# weichen-a-2.net
KiCad netlist of a schematic drawn in EAGLE
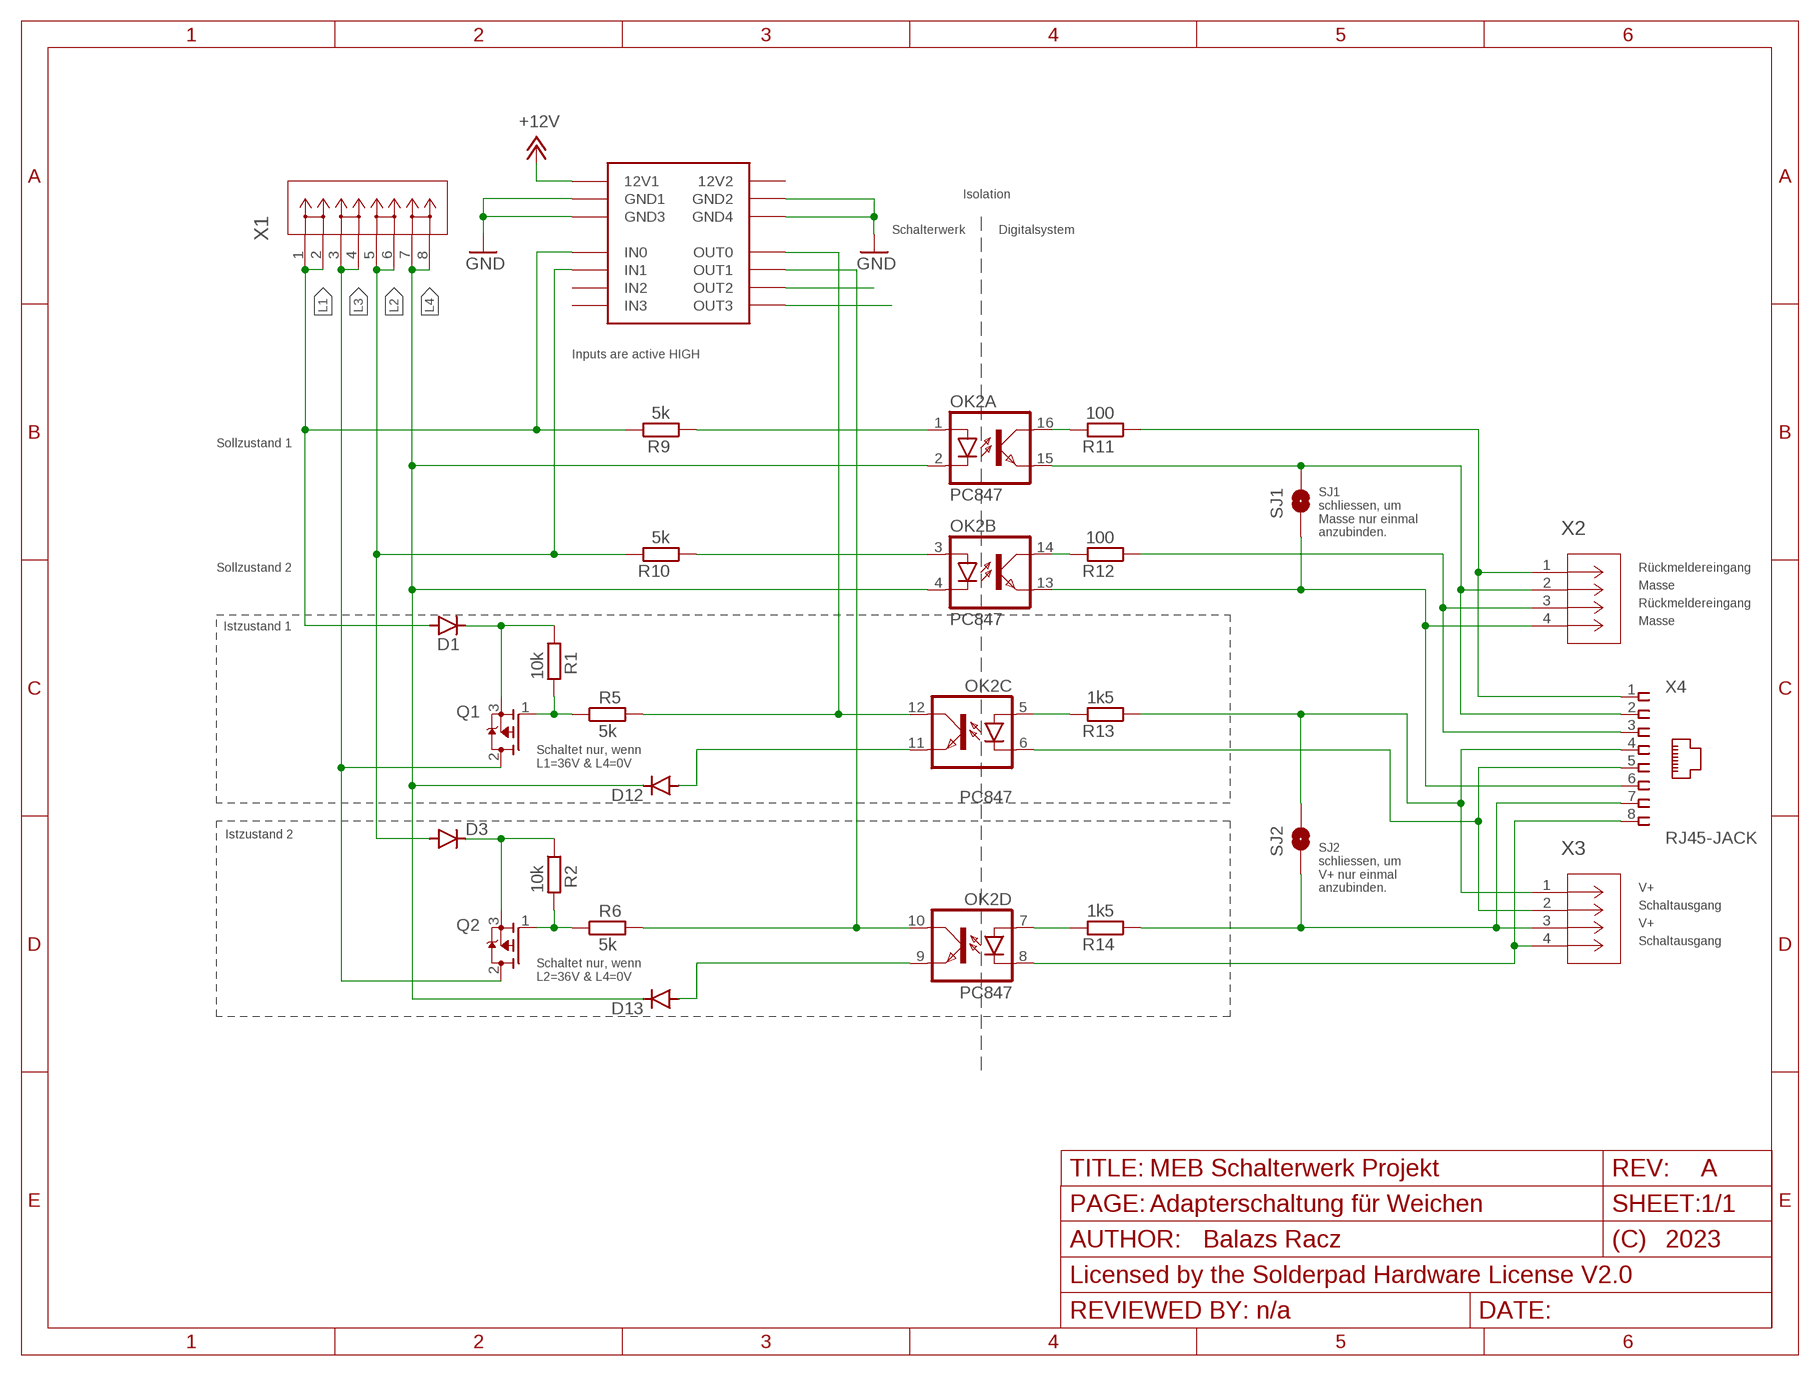
[diagram p0: schematic, sheet 1]

(export (version "E")
  (design (tool "Eeschema 10.0.6"))
  (components
    (comp (ref "D1")
      (value "DIODE-DO214AC")
      (footprint "eagle-import:DO214AC")
      (libsource (lib "eagle-import") (part "DIODE-DO214AC"))
    )
    (comp (ref "D3")
      (value "DIODE-DO214AC")
      (footprint "eagle-import:DO214AC")
      (libsource (lib "eagle-import") (part "DIODE-DO214AC"))
    )
    (comp (ref "D12")
      (value "DIODE-MINIMELF")
      (footprint "eagle-import:MINIMELF")
      (libsource (lib "eagle-import") (part "DIODE-MINIMELF"))
    )
    (comp (ref "D13")
      (value "DIODE-MINIMELF")
      (footprint "eagle-import:MINIMELF")
      (libsource (lib "eagle-import") (part "DIODE-MINIMELF"))
    )
    (comp (ref "OK2")
      (value "PC847")
      (footprint "eagle-import:DIL16")
      (libsource (lib "eagle-import") (part "PC847"))
    )
    (comp (ref "Q1")
      (value "P-MOSFET")
      (footprint "eagle-import:DPAK-2")
      (fields (field (name "MANUFACTURER") "Infineon"))
      (libsource (lib "eagle-import") (part "P-MOSFET"))
    )
    (comp (ref "Q2")
      (value "P-MOSFET")
      (footprint "eagle-import:DPAK-2")
      (fields (field (name "MANUFACTURER") "Infineon"))
      (libsource (lib "eagle-import") (part "P-MOSFET"))
    )
    (comp (ref "R1")
      (value "10k")
      (footprint "eagle-import:R0805")
      (libsource (lib "eagle-import") (part "R-EU_R0805"))
    )
    (comp (ref "R2")
      (value "10k")
      (footprint "eagle-import:R0805")
      (libsource (lib "eagle-import") (part "R-EU_R0805"))
    )
    (comp (ref "R5")
      (value "5k")
      (footprint "eagle-import:R0805")
      (libsource (lib "eagle-import") (part "R-EU_R0805"))
    )
    (comp (ref "R6")
      (value "5k")
      (footprint "eagle-import:R0805")
      (libsource (lib "eagle-import") (part "R-EU_R0805"))
    )
    (comp (ref "R9")
      (value "5k")
      (footprint "eagle-import:R0805")
      (libsource (lib "eagle-import") (part "R-EU_R0805"))
    )
    (comp (ref "R10")
      (value "5k")
      (footprint "eagle-import:R0805")
      (libsource (lib "eagle-import") (part "R-EU_R0805"))
    )
    (comp (ref "R11")
      (value "100")
      (footprint "eagle-import:R0805")
      (libsource (lib "eagle-import") (part "R-EU_R0805"))
    )
    (comp (ref "R12")
      (value "100")
      (footprint "eagle-import:R0805")
      (libsource (lib "eagle-import") (part "R-EU_R0805"))
    )
    (comp (ref "R13")
      (value "1k5")
      (footprint "eagle-import:R0805")
      (libsource (lib "eagle-import") (part "R-EU_R0805"))
    )
    (comp (ref "R14")
      (value "1k5")
      (footprint "eagle-import:R0805")
      (libsource (lib "eagle-import") (part "R-EU_R0805"))
    )
    (comp (ref "SJ1")
      (value "SJRND2")
      (footprint "eagle-import:SJ_RND2")
      (libsource (lib "eagle-import") (part "SJRND2"))
    )
    (comp (ref "SJ2")
      (value "SJRND2")
      (footprint "eagle-import:SJ_RND2")
      (libsource (lib "eagle-import") (part "SJRND2"))
    )
    (comp (ref "X1")
      (value "PHNX_4P_508CONN_1017493")
      (footprint "eagle-import:PHNX_4P_508")
      (fields
        (field (name "MANUFACTURER_PART_NUMBER") "1017505")
        (field (name "COPYRIGHT") "Copyright (C) 2023 Ultra Librarian. All rights reserved.")
      )
      (libsource (lib "eagle-import") (part "PHNX_4P_508CONN_1017493"))
    )
    (comp (ref "X2")
      (value "PHNX_4P_350CONN_1984989_PXC")
      (footprint "eagle-import:PHNX_4P_350")
      (fields
        (field (name "MANUFACTURER_PART_NUMBER") "1984989")
        (field (name "COPYRIGHT") "Copyright (C) 2023 Ultra Librarian. All rights reserved.")
      )
      (libsource (lib "eagle-import") (part "PHNX_4P_350CONN_1984989_PXC"))
    )
    (comp (ref "X3")
      (value "PHNX_4P_350CONN_1984989_PXC")
      (footprint "eagle-import:PHNX_4P_350")
      (fields
        (field (name "MANUFACTURER_PART_NUMBER") "1984989")
        (field (name "COPYRIGHT") "Copyright (C) 2023 Ultra Librarian. All rights reserved.")
      )
      (libsource (lib "eagle-import") (part "PHNX_4P_350CONN_1984989_PXC"))
    )
    (comp (ref "X4")
      (value "RJ45-JACK")
      (footprint "eagle-import:RJ45-PULSE-E5J88")
      (libsource (lib "eagle-import") (part "RJ45-JACKRJ45-PULSE-E5J00"))
    )
    (comp (ref "X5")
      (value "IO-HAT")
      (footprint "eagle-import:IOBOARD")
      (libsource (lib "eagle-import") (part "IO-HAT"))
    )
  )
  (nets
    (net (code "1") (name "+12V") (class "Default")
      (node (ref "X5") (pin "P$1") (pinfunction "12V1_P$1") (pintype "power_in"))
    )
    (net (code "2") (name "/12V2") (class "Default")
      (node (ref "X5") (pin "P$22") (pinfunction "12V2_P$22") (pintype "power_in"))
    )
    (net (code "3") (name "GND") (class "Default")
      (node (ref "X5") (pin "P$11") (pinfunction "GND3_P$11") (pintype "power_in"))
      (node (ref "X5") (pin "P$12") (pinfunction "GND4_P$12") (pintype "power_in"))
      (node (ref "X5") (pin "P$2") (pinfunction "GND1_P$2") (pintype "power_in"))
      (node (ref "X5") (pin "P$21") (pinfunction "GND2_P$21") (pintype "power_in"))
    )
    (net (code "4") (name "L1") (class "Default")
      (node (ref "D1") (pin "A") (pinfunction "A_A") (pintype "passive"))
      (node (ref "R9") (pin "2") (pinfunction "2_2") (pintype "passive"))
      (node (ref "X1") (pin "1") (pinfunction "1_1") (pintype "passive"))
      (node (ref "X1") (pin "2") (pinfunction "2_2") (pintype "passive"))
      (node (ref "X5") (pin "P$3") (pinfunction "IN0_P$3") (pintype "input"))
    )
    (net (code "5") (name "L2") (class "Default")
      (node (ref "D3") (pin "A") (pinfunction "A_A") (pintype "passive"))
      (node (ref "R10") (pin "2") (pinfunction "2_2") (pintype "passive"))
      (node (ref "X1") (pin "5") (pinfunction "5_5") (pintype "passive"))
      (node (ref "X1") (pin "6") (pinfunction "6_6") (pintype "passive"))
      (node (ref "X5") (pin "P$4") (pinfunction "IN1_P$4") (pintype "input"))
    )
    (net (code "6") (name "L3") (class "Default")
      (node (ref "Q1") (pin "2") (pinfunction "D_2") (pintype "passive"))
      (node (ref "Q2") (pin "2") (pinfunction "D_2") (pintype "passive"))
      (node (ref "X1") (pin "3") (pinfunction "3_3") (pintype "passive"))
      (node (ref "X1") (pin "4") (pinfunction "4_4") (pintype "passive"))
    )
    (net (code "7") (name "L4") (class "Default")
      (node (ref "D12") (pin "C") (pinfunction "C_C") (pintype "passive"))
      (node (ref "D13") (pin "C") (pinfunction "C_C") (pintype "passive"))
      (node (ref "OK2") (pin "2") (pinfunction "C_2") (pintype "passive"))
      (node (ref "OK2") (pin "4") (pinfunction "C_4") (pintype "passive"))
      (node (ref "X1") (pin "7") (pinfunction "7_7") (pintype "passive"))
      (node (ref "X1") (pin "8") (pinfunction "8_8") (pintype "passive"))
    )
    (net (code "8") (name "Net-(OK2A-A)") (class "Default")
      (node (ref "OK2") (pin "1") (pinfunction "A_1") (pintype "passive"))
      (node (ref "R9") (pin "1") (pinfunction "1_1") (pintype "passive"))
    )
    (net (code "9") (name "Net-(OK2A-COL)") (class "Default")
      (node (ref "OK2") (pin "16") (pinfunction "COL_16") (pintype "passive"))
      (node (ref "R11") (pin "2") (pinfunction "2_2") (pintype "passive"))
    )
    (net (code "10") (name "Net-(OK2A-EMIT)") (class "Default")
      (node (ref "OK2") (pin "15") (pinfunction "EMIT_15") (pintype "passive"))
      (node (ref "SJ1") (pin "P$2") (pinfunction "2_P$2") (pintype "passive"))
      (node (ref "X2") (pin "2") (pinfunction "2_2") (pintype "passive"))
      (node (ref "X4") (pin "2") (pinfunction "2_2") (pintype "passive"))
    )
    (net (code "11") (name "Net-(OK2B-A)") (class "Default")
      (node (ref "OK2") (pin "3") (pinfunction "A_3") (pintype "passive"))
      (node (ref "R10") (pin "1") (pinfunction "1_1") (pintype "passive"))
    )
    (net (code "12") (name "Net-(OK2B-COL)") (class "Default")
      (node (ref "OK2") (pin "14") (pinfunction "COL_14") (pintype "passive"))
      (node (ref "R12") (pin "2") (pinfunction "2_2") (pintype "passive"))
    )
    (net (code "13") (name "Net-(OK2B-EMIT)") (class "Default")
      (node (ref "OK2") (pin "13") (pinfunction "EMIT_13") (pintype "passive"))
      (node (ref "SJ1") (pin "P$1") (pinfunction "1_P$1") (pintype "passive"))
      (node (ref "X2") (pin "4") (pinfunction "4_4") (pintype "passive"))
      (node (ref "X4") (pin "6") (pinfunction "6_6") (pintype "passive"))
    )
    (net (code "14") (name "Net-(OK2C-A)") (class "Default")
      (node (ref "OK2") (pin "5") (pinfunction "A_5") (pintype "passive"))
      (node (ref "R13") (pin "2") (pinfunction "2_2") (pintype "passive"))
    )
    (net (code "15") (name "Net-(OK2C-C)") (class "Default")
      (node (ref "OK2") (pin "6") (pinfunction "C_6") (pintype "passive"))
      (node (ref "X3") (pin "2") (pinfunction "2_2") (pintype "passive"))
      (node (ref "X4") (pin "5") (pinfunction "5_5") (pintype "passive"))
    )
    (net (code "16") (name "Net-(OK2C-COL)") (class "Default")
      (node (ref "OK2") (pin "12") (pinfunction "COL_12") (pintype "passive"))
      (node (ref "R5") (pin "2") (pinfunction "2_2") (pintype "passive"))
      (node (ref "X5") (pin "P$20") (pinfunction "OUT0_P$20") (pintype "open_collector"))
    )
    (net (code "17") (name "Net-(OK2C-EMIT)") (class "Default")
      (node (ref "D12") (pin "A") (pinfunction "A_A") (pintype "passive"))
      (node (ref "OK2") (pin "11") (pinfunction "EMIT_11") (pintype "passive"))
    )
    (net (code "18") (name "Net-(OK2D-A)") (class "Default")
      (node (ref "OK2") (pin "7") (pinfunction "A_7") (pintype "passive"))
      (node (ref "R14") (pin "2") (pinfunction "2_2") (pintype "passive"))
    )
    (net (code "19") (name "Net-(OK2D-C)") (class "Default")
      (node (ref "OK2") (pin "8") (pinfunction "C_8") (pintype "passive"))
      (node (ref "X3") (pin "4") (pinfunction "4_4") (pintype "passive"))
      (node (ref "X4") (pin "8") (pinfunction "8_8") (pintype "passive"))
    )
    (net (code "20") (name "Net-(OK2D-COL)") (class "Default")
      (node (ref "OK2") (pin "10") (pinfunction "COL_10") (pintype "passive"))
      (node (ref "R6") (pin "2") (pinfunction "2_2") (pintype "passive"))
      (node (ref "X5") (pin "P$19") (pinfunction "OUT1_P$19") (pintype "open_collector"))
    )
    (net (code "21") (name "Net-(OK2D-EMIT)") (class "Default")
      (node (ref "D13") (pin "A") (pinfunction "A_A") (pintype "passive"))
      (node (ref "OK2") (pin "9") (pinfunction "EMIT_9") (pintype "passive"))
    )
    (net (code "22") (name "Net-(Q1-G)") (class "Default")
      (node (ref "Q1") (pin "1") (pinfunction "G_1") (pintype "passive"))
      (node (ref "R1") (pin "2") (pinfunction "2_2") (pintype "passive"))
      (node (ref "R5") (pin "1") (pinfunction "1_1") (pintype "passive"))
    )
    (net (code "23") (name "Net-(Q1-S)") (class "Default")
      (node (ref "D1") (pin "C") (pinfunction "C_C") (pintype "passive"))
      (node (ref "Q1") (pin "3") (pinfunction "S_3") (pintype "passive"))
      (node (ref "R1") (pin "1") (pinfunction "1_1") (pintype "passive"))
    )
    (net (code "24") (name "Net-(Q2-G)") (class "Default")
      (node (ref "Q2") (pin "1") (pinfunction "G_1") (pintype "passive"))
      (node (ref "R2") (pin "2") (pinfunction "2_2") (pintype "passive"))
      (node (ref "R6") (pin "1") (pinfunction "1_1") (pintype "passive"))
    )
    (net (code "25") (name "Net-(Q2-S)") (class "Default")
      (node (ref "D3") (pin "C") (pinfunction "C_C") (pintype "passive"))
      (node (ref "Q2") (pin "3") (pinfunction "S_3") (pintype "passive"))
      (node (ref "R2") (pin "1") (pinfunction "1_1") (pintype "passive"))
    )
    (net (code "26") (name "Net-(R11-Pad1)") (class "Default")
      (node (ref "R11") (pin "1") (pinfunction "1_1") (pintype "passive"))
      (node (ref "X2") (pin "1") (pinfunction "1_1") (pintype "passive"))
      (node (ref "X4") (pin "1") (pinfunction "1_1") (pintype "passive"))
    )
    (net (code "27") (name "Net-(R12-Pad1)") (class "Default")
      (node (ref "R12") (pin "1") (pinfunction "1_1") (pintype "passive"))
      (node (ref "X2") (pin "3") (pinfunction "3_3") (pintype "passive"))
      (node (ref "X4") (pin "3") (pinfunction "3_3") (pintype "passive"))
    )
    (net (code "28") (name "Net-(SJ2-1)") (class "Default")
      (node (ref "R14") (pin "1") (pinfunction "1_1") (pintype "passive"))
      (node (ref "SJ2") (pin "P$1") (pinfunction "1_P$1") (pintype "passive"))
      (node (ref "X3") (pin "3") (pinfunction "3_3") (pintype "passive"))
      (node (ref "X4") (pin "7") (pinfunction "7_7") (pintype "passive"))
    )
    (net (code "29") (name "Net-(SJ2-2)") (class "Default")
      (node (ref "R13") (pin "1") (pinfunction "1_1") (pintype "passive"))
      (node (ref "SJ2") (pin "P$2") (pinfunction "2_P$2") (pintype "passive"))
      (node (ref "X3") (pin "1") (pinfunction "1_1") (pintype "passive"))
      (node (ref "X4") (pin "4") (pinfunction "4_4") (pintype "passive"))
    )
    (net (code "30") (name "unconnected-(X5A-IN2-PadP$5)") (class "Default")
      (node (ref "X5") (pin "P$5") (pinfunction "IN2_P$5") (pintype "input"))
    )
    (net (code "31") (name "unconnected-(X5A-IN3-PadP$6)") (class "Default")
      (node (ref "X5") (pin "P$6") (pinfunction "IN3_P$6") (pintype "input"))
    )
    (net (code "32") (name "unconnected-(X5A-OUT2-PadP$18)") (class "Default")
      (node (ref "X5") (pin "P$18") (pinfunction "OUT2_P$18") (pintype "open_collector"))
    )
    (net (code "33") (name "unconnected-(X5A-OUT3-PadP$17)") (class "Default")
      (node (ref "X5") (pin "P$17") (pinfunction "OUT3_P$17") (pintype "open_collector"))
    )
  )
)
